# pcb_univ_3-9-0-x-rev3.net
KiCad netlist of a schematic drawn in EAGLE
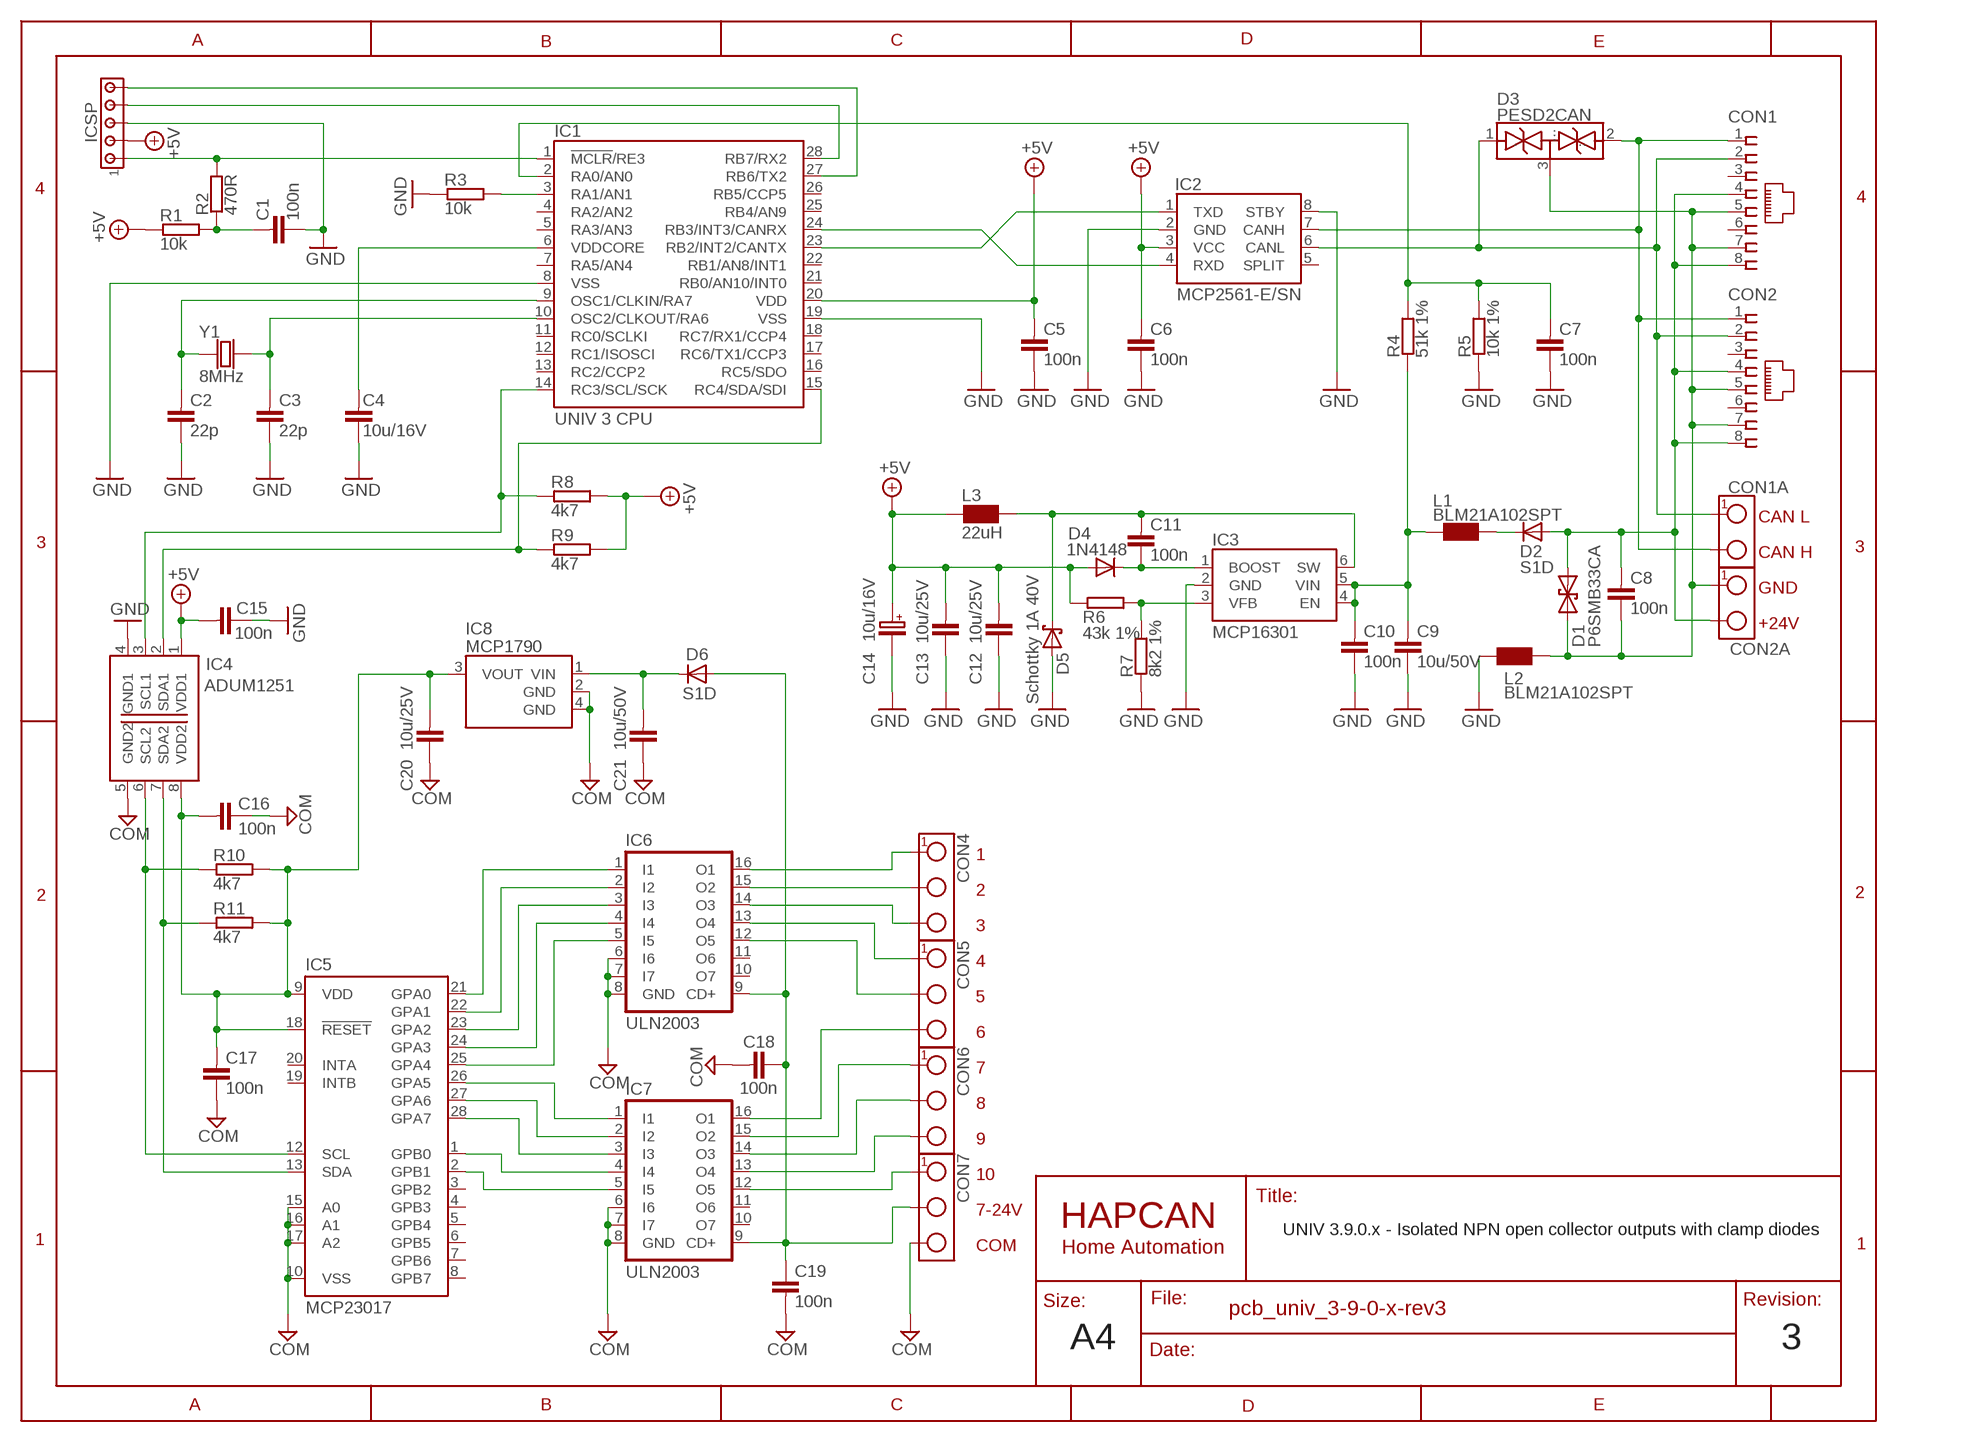
[diagram p0: schematic, sheet 1]

(export (version "E")
  (design (tool "Eeschema 10.0.6"))
  (components
    (comp (ref "C1")
      (value "100n")
      (footprint "eagle-import:0805")
      (libsource (lib "eagle-import") (part "CAPACITOR0805"))
    )
    (comp (ref "C2")
      (value "22p")
      (footprint "eagle-import:0805")
      (libsource (lib "eagle-import") (part "CAPACITOR0805"))
    )
    (comp (ref "C3")
      (value "22p")
      (footprint "eagle-import:0805")
      (libsource (lib "eagle-import") (part "CAPACITOR0805"))
    )
    (comp (ref "C4")
      (value "10u/16V")
      (footprint "eagle-import:0805")
      (libsource (lib "eagle-import") (part "CAPACITOR0805"))
    )
    (comp (ref "C5")
      (value "100n")
      (footprint "eagle-import:0805")
      (libsource (lib "eagle-import") (part "CAPACITOR0805"))
    )
    (comp (ref "C6")
      (value "100n")
      (footprint "eagle-import:0805")
      (libsource (lib "eagle-import") (part "CAPACITOR0805"))
    )
    (comp (ref "C7")
      (value "100n")
      (footprint "eagle-import:0805")
      (libsource (lib "eagle-import") (part "CAPACITOR0805"))
    )
    (comp (ref "C8")
      (value "100n")
      (footprint "eagle-import:0805")
      (libsource (lib "eagle-import") (part "CAPACITOR0805"))
    )
    (comp (ref "C9")
      (value "10u/50V")
      (footprint "eagle-import:1210")
      (libsource (lib "eagle-import") (part "CAPACITOR1210"))
    )
    (comp (ref "C10")
      (value "100n")
      (footprint "eagle-import:0805")
      (libsource (lib "eagle-import") (part "CAPACITOR0805"))
    )
    (comp (ref "C11")
      (value "100n")
      (footprint "eagle-import:0805")
      (libsource (lib "eagle-import") (part "CAPACITOR0805"))
    )
    (comp (ref "C12")
      (value "10u/25V")
      (footprint "eagle-import:1206")
      (libsource (lib "eagle-import") (part "CAPACITOR1206"))
    )
    (comp (ref "C13")
      (value "10u/25V")
      (footprint "eagle-import:1206")
      (libsource (lib "eagle-import") (part "CAPACITOR1206"))
    )
    (comp (ref "C14")
      (value "10u/16V")
      (footprint "eagle-import:SMC_B")
      (libsource (lib "eagle-import") (part "CAPACITOR-POLARIZED-SMC_B"))
    )
    (comp (ref "C15")
      (value "100n")
      (footprint "eagle-import:0805")
      (libsource (lib "eagle-import") (part "CAPACITOR0805"))
    )
    (comp (ref "C16")
      (value "100n")
      (footprint "eagle-import:0805")
      (libsource (lib "eagle-import") (part "CAPACITOR0805"))
    )
    (comp (ref "C17")
      (value "100n")
      (footprint "eagle-import:0805")
      (libsource (lib "eagle-import") (part "CAPACITOR0805"))
    )
    (comp (ref "C18")
      (value "100n")
      (footprint "eagle-import:0805")
      (libsource (lib "eagle-import") (part "CAPACITOR0805"))
    )
    (comp (ref "C19")
      (value "100n")
      (footprint "eagle-import:0805")
      (libsource (lib "eagle-import") (part "CAPACITOR0805"))
    )
    (comp (ref "C20")
      (value "10u/25V")
      (footprint "eagle-import:1206")
      (libsource (lib "eagle-import") (part "CAPACITOR1206"))
    )
    (comp (ref "C21")
      (value "10u/50V")
      (footprint "eagle-import:1210")
      (libsource (lib "eagle-import") (part "CAPACITOR1210"))
    )
    (comp (ref "CON1")
      (value "RJ45-SOCKET")
      (footprint "eagle-import:RJ45-PCB-SOCKET")
      (libsource (lib "eagle-import") (part "RJ45-SOCKET"))
    )
    (comp (ref "CON1A")
      (value "TERMINAL-2")
      (footprint "eagle-import:ARK2-5X10,5MM")
      (libsource (lib "eagle-import") (part "TERMINAL-2-5X10,5MM"))
    )
    (comp (ref "CON2")
      (value "RJ45-SOCKET")
      (footprint "eagle-import:RJ45-PCB-SOCKET")
      (libsource (lib "eagle-import") (part "RJ45-SOCKET"))
    )
    (comp (ref "CON2A")
      (value "TERMINAL-2")
      (footprint "eagle-import:ARK2-5X10,5MM")
      (libsource (lib "eagle-import") (part "TERMINAL-2-5X10,5MM"))
    )
    (comp (ref "CON4")
      (value "TERMINAL-3-3.81X8MM")
      (footprint "eagle-import:ARK3-3.81X8MM")
      (libsource (lib "eagle-import") (part "TERMINAL-3-3.81X8MM"))
    )
    (comp (ref "CON5")
      (value "TERMINAL-3-3.81X8MM")
      (footprint "eagle-import:ARK3-3.81X8MM")
      (libsource (lib "eagle-import") (part "TERMINAL-3-3.81X8MM"))
    )
    (comp (ref "CON6")
      (value "TERMINAL-3-3.81X8MM")
      (footprint "eagle-import:ARK3-3.81X8MM")
      (libsource (lib "eagle-import") (part "TERMINAL-3-3.81X8MM"))
    )
    (comp (ref "CON7")
      (value "TERMINAL-3-3.81X8MM")
      (footprint "eagle-import:ARK3-3.81X8MM")
      (libsource (lib "eagle-import") (part "TERMINAL-3-3.81X8MM"))
    )
    (comp (ref "D1")
      (value "P6SMB33CA")
      (footprint "eagle-import:DO-214_TRANSIL2")
      (libsource (lib "eagle-import") (part "DIODE_TRANSIL2"))
    )
    (comp (ref "D2")
      (value "S1D")
      (footprint "eagle-import:DO-214")
      (libsource (lib "eagle-import") (part "DIODE_DO-214"))
    )
    (comp (ref "D3")
      (value "PESD2CAN")
      (footprint "eagle-import:SOT-23")
      (libsource (lib "eagle-import") (part "PESD2CANSOT-23"))
    )
    (comp (ref "D4")
      (value "1N4148")
      (footprint "eagle-import:0805")
      (libsource (lib "eagle-import") (part "DIODE_0805"))
    )
    (comp (ref "D5")
      (value "Schottky 1A 40V")
      (footprint "eagle-import:DO-214")
      (libsource (lib "eagle-import") (part "DIODE_TRANSIL1_DO214"))
    )
    (comp (ref "D6")
      (value "S1D")
      (footprint "eagle-import:DO-214")
      (libsource (lib "eagle-import") (part "DIODE_DO-214"))
    )
    (comp (ref "IC1")
      (value "UNIV 3 CPU")
      (footprint "eagle-import:UNIV3CPU")
      (libsource (lib "eagle-import") (part "UNIV3CPU-I/SO"))
    )
    (comp (ref "IC2")
      (value "MCP2561-E/SN")
      (footprint "eagle-import:SO-08")
      (libsource (lib "eagle-import") (part "MCP2561-E/SN"))
    )
    (comp (ref "IC3")
      (value "MCP16301")
      (footprint "eagle-import:SOT-23-6")
      (libsource (lib "eagle-import") (part "MCP16301SOT23-6"))
    )
    (comp (ref "IC4")
      (value "ADUM1251")
      (footprint "eagle-import:SO-08")
      (libsource (lib "eagle-import") (part "ADUM1251"))
    )
    (comp (ref "IC5")
      (value "MCP23017")
      (footprint "eagle-import:SO-28W")
      (libsource (lib "eagle-import") (part "MCP23017-SO"))
    )
    (comp (ref "IC6")
      (value "ULN2003")
      (footprint "eagle-import:SO-16")
      (libsource (lib "eagle-import") (part "ULN2003"))
    )
    (comp (ref "IC7")
      (value "ULN2003")
      (footprint "eagle-import:SO-16")
      (libsource (lib "eagle-import") (part "ULN2003"))
    )
    (comp (ref "IC8")
      (value "MCP1790")
      (footprint "eagle-import:SOT-223")
      (libsource (lib "eagle-import") (part "MCP1790"))
    )
    (comp (ref "ICSP")
      (value "HEADER5")
      (footprint "eagle-import:SIP-5")
      (libsource (lib "eagle-import") (part "HEADER5"))
    )
    (comp (ref "L1")
      (value "BLM21A102SPT")
      (footprint "eagle-import:0805")
      (libsource (lib "eagle-import") (part "CHOKE0805"))
    )
    (comp (ref "L2")
      (value "BLM21A102SPT")
      (footprint "eagle-import:0805")
      (libsource (lib "eagle-import") (part "CHOKE0805"))
    )
    (comp (ref "L3")
      (value "22uH")
      (footprint "eagle-import:CHOKE-DER0705")
      (libsource (lib "eagle-import") (part "CHOKEDER0705"))
    )
    (comp (ref "R1")
      (value "10k")
      (footprint "eagle-import:0805")
      (libsource (lib "eagle-import") (part "RESISTOR0805"))
    )
    (comp (ref "R2")
      (value "470R")
      (footprint "eagle-import:0805")
      (libsource (lib "eagle-import") (part "RESISTOR0805"))
    )
    (comp (ref "R3")
      (value "10k")
      (footprint "eagle-import:0805")
      (libsource (lib "eagle-import") (part "RESISTOR0805"))
    )
    (comp (ref "R4")
      (value "51k 1%")
      (footprint "eagle-import:0805")
      (libsource (lib "eagle-import") (part "RESISTOR0805"))
    )
    (comp (ref "R5")
      (value "10k 1%")
      (footprint "eagle-import:0805")
      (libsource (lib "eagle-import") (part "RESISTOR0805"))
    )
    (comp (ref "R6")
      (value "43k 1%")
      (footprint "eagle-import:0805")
      (libsource (lib "eagle-import") (part "RESISTOR0805"))
    )
    (comp (ref "R7")
      (value "8k2 1%")
      (footprint "eagle-import:0805")
      (libsource (lib "eagle-import") (part "RESISTOR0805"))
    )
    (comp (ref "R8")
      (value "4k7")
      (footprint "eagle-import:0805")
      (libsource (lib "eagle-import") (part "RESISTOR0805"))
    )
    (comp (ref "R9")
      (value "4k7")
      (footprint "eagle-import:0805")
      (libsource (lib "eagle-import") (part "RESISTOR0805"))
    )
    (comp (ref "R10")
      (value "4k7")
      (footprint "eagle-import:0805")
      (libsource (lib "eagle-import") (part "RESISTOR0805"))
    )
    (comp (ref "R11")
      (value "4k7")
      (footprint "eagle-import:0805")
      (libsource (lib "eagle-import") (part "RESISTOR0805"))
    )
    (comp (ref "Y1")
      (value "8MHz")
      (footprint "eagle-import:CRYSTAL-HC49V")
      (libsource (lib "eagle-import") (part "CRYSTAL-HC49V"))
    )
  )
  (nets
    (net (code "1") (name "+5V") (class "Default")
      (node (ref "C12") (pin "1") (pinfunction "1_1") (pintype "passive"))
      (node (ref "C13") (pin "1") (pinfunction "1_1") (pintype "passive"))
      (node (ref "C14") (pin "+") (pinfunction "1_+") (pintype "passive"))
      (node (ref "C15") (pin "1") (pinfunction "1_1") (pintype "passive"))
      (node (ref "C5") (pin "1") (pinfunction "1_1") (pintype "passive"))
      (node (ref "C6") (pin "1") (pinfunction "1_1") (pintype "passive"))
      (node (ref "D4") (pin "2") (pinfunction "A_2") (pintype "passive"))
      (node (ref "IC1") (pin "20") (pinfunction "VDD_20") (pintype "bidirectional"))
      (node (ref "IC2") (pin "3") (pinfunction "VCC_3") (pintype "bidirectional"))
      (node (ref "IC4") (pin "1") (pinfunction "VDD1_1") (pintype "bidirectional"))
      (node (ref "ICSP") (pin "2") (pinfunction "2_2") (pintype "passive"))
      (node (ref "L3") (pin "1") (pinfunction "1_1") (pintype "passive"))
      (node (ref "R1") (pin "1") (pinfunction "1_1") (pintype "passive"))
      (node (ref "R6") (pin "1") (pinfunction "1_1") (pintype "passive"))
      (node (ref "R8") (pin "2") (pinfunction "2_2") (pintype "passive"))
      (node (ref "R9") (pin "2") (pinfunction "2_2") (pintype "passive"))
    )
    (net (code "2") (name "COM") (class "Default")
      (node (ref "C16") (pin "2") (pinfunction "2_2") (pintype "passive"))
      (node (ref "C17") (pin "2") (pinfunction "2_2") (pintype "passive"))
      (node (ref "C18") (pin "1") (pinfunction "1_1") (pintype "passive"))
      (node (ref "C19") (pin "1") (pinfunction "1_1") (pintype "passive"))
      (node (ref "C20") (pin "2") (pinfunction "2_2") (pintype "passive"))
      (node (ref "C21") (pin "2") (pinfunction "2_2") (pintype "passive"))
      (node (ref "CON7") (pin "3") (pinfunction "3_3") (pintype "passive"))
      (node (ref "IC4") (pin "5") (pinfunction "GND2_5") (pintype "bidirectional"))
      (node (ref "IC5") (pin "10") (pinfunction "VSS_10") (pintype "bidirectional"))
      (node (ref "IC5") (pin "15") (pinfunction "A0_15") (pintype "input"))
      (node (ref "IC5") (pin "16") (pinfunction "A1_16") (pintype "input"))
      (node (ref "IC5") (pin "17") (pinfunction "A2_17") (pintype "input"))
      (node (ref "IC6") (pin "6") (pinfunction "I6_6") (pintype "input"))
      (node (ref "IC6") (pin "7") (pinfunction "I7_7") (pintype "input"))
      (node (ref "IC6") (pin "8") (pinfunction "GND_8") (pintype "power_in"))
      (node (ref "IC7") (pin "6") (pinfunction "I6_6") (pintype "input"))
      (node (ref "IC7") (pin "7") (pinfunction "I7_7") (pintype "input"))
      (node (ref "IC7") (pin "8") (pinfunction "GND_8") (pintype "power_in"))
      (node (ref "IC8") (pin "2") (pinfunction "GND_2") (pintype "bidirectional"))
      (node (ref "IC8") (pin "4") (pinfunction "GND_4") (pintype "bidirectional"))
    )
    (net (code "3") (name "GND") (class "Default")
      (node (ref "C1") (pin "2") (pinfunction "2_2") (pintype "passive"))
      (node (ref "C10") (pin "2") (pinfunction "2_2") (pintype "passive"))
      (node (ref "C12") (pin "2") (pinfunction "2_2") (pintype "passive"))
      (node (ref "C13") (pin "2") (pinfunction "2_2") (pintype "passive"))
      (node (ref "C14") (pin "-") (pinfunction "2_-") (pintype "passive"))
      (node (ref "C15") (pin "2") (pinfunction "2_2") (pintype "passive"))
      (node (ref "C2") (pin "2") (pinfunction "2_2") (pintype "passive"))
      (node (ref "C3") (pin "2") (pinfunction "2_2") (pintype "passive"))
      (node (ref "C4") (pin "2") (pinfunction "2_2") (pintype "passive"))
      (node (ref "C5") (pin "2") (pinfunction "2_2") (pintype "passive"))
      (node (ref "C6") (pin "2") (pinfunction "2_2") (pintype "passive"))
      (node (ref "C7") (pin "2") (pinfunction "2_2") (pintype "passive"))
      (node (ref "C9") (pin "2") (pinfunction "2_2") (pintype "passive"))
      (node (ref "D5") (pin "A") (pinfunction "A_A") (pintype "passive"))
      (node (ref "IC1") (pin "19") (pinfunction "VSS_19") (pintype "bidirectional"))
      (node (ref "IC1") (pin "8") (pinfunction "VSS_8") (pintype "bidirectional"))
      (node (ref "IC2") (pin "2") (pinfunction "GND_2") (pintype "bidirectional"))
      (node (ref "IC2") (pin "8") (pinfunction "STBY_8") (pintype "bidirectional"))
      (node (ref "IC3") (pin "2") (pinfunction "GND_2") (pintype "bidirectional"))
      (node (ref "IC4") (pin "4") (pinfunction "GND1_4") (pintype "bidirectional"))
      (node (ref "ICSP") (pin "3") (pinfunction "3_3") (pintype "passive"))
      (node (ref "L2") (pin "1") (pinfunction "1_1") (pintype "passive"))
      (node (ref "R3") (pin "1") (pinfunction "1_1") (pintype "passive"))
      (node (ref "R5") (pin "1") (pinfunction "1_1") (pintype "passive"))
      (node (ref "R7") (pin "1") (pinfunction "1_1") (pintype "passive"))
    )
    (net (code "4") (name "Net-(C1-Pad1)") (class "Default")
      (node (ref "C1") (pin "1") (pinfunction "1_1") (pintype "passive"))
      (node (ref "R1") (pin "2") (pinfunction "2_2") (pintype "passive"))
      (node (ref "R2") (pin "1") (pinfunction "1_1") (pintype "passive"))
    )
    (net (code "5") (name "Net-(D1-1)") (class "Default")
      (node (ref "C8") (pin "2") (pinfunction "2_2") (pintype "passive"))
      (node (ref "CON1") (pin "5") (pinfunction "5_5") (pintype "passive"))
      (node (ref "CON1") (pin "7") (pinfunction "7_7") (pintype "passive"))
      (node (ref "CON2") (pin "5") (pinfunction "5_5") (pintype "passive"))
      (node (ref "CON2") (pin "7") (pinfunction "7_7") (pintype "passive"))
      (node (ref "CON2A") (pin "1") (pinfunction "1_1") (pintype "passive"))
      (node (ref "D1") (pin "A") (pinfunction "1_A") (pintype "passive"))
      (node (ref "D3") (pin "3") (pinfunction "..._3") (pintype "bidirectional"))
      (node (ref "L2") (pin "2") (pinfunction "2_2") (pintype "passive"))
    )
    (net (code "6") (name "Net-(D1-2)") (class "Default")
      (node (ref "C8") (pin "1") (pinfunction "1_1") (pintype "passive"))
      (node (ref "CON1") (pin "4") (pinfunction "4_4") (pintype "passive"))
      (node (ref "CON1") (pin "8") (pinfunction "8_8") (pintype "passive"))
      (node (ref "CON2") (pin "4") (pinfunction "4_4") (pintype "passive"))
      (node (ref "CON2") (pin "8") (pinfunction "8_8") (pintype "passive"))
      (node (ref "CON2A") (pin "2") (pinfunction "2_2") (pintype "passive"))
      (node (ref "D1") (pin "C") (pinfunction "2_C") (pintype "passive"))
      (node (ref "D2") (pin "A") (pinfunction "A_A") (pintype "passive"))
    )
    (net (code "7") (name "Net-(D2-PadC)") (class "Default")
      (node (ref "D2") (pin "C") (pinfunction "C_C") (pintype "passive"))
      (node (ref "L1") (pin "2") (pinfunction "2_2") (pintype "passive"))
    )
    (net (code "8") (name "Net-(D3-.)") (class "Default")
      (node (ref "CON1") (pin "2") (pinfunction "2_2") (pintype "passive"))
      (node (ref "CON1A") (pin "1") (pinfunction "1_1") (pintype "passive"))
      (node (ref "CON2") (pin "2") (pinfunction "2_2") (pintype "passive"))
      (node (ref "D3") (pin "1") (pinfunction "._1") (pintype "bidirectional"))
      (node (ref "IC2") (pin "6") (pinfunction "CANL_6") (pintype "bidirectional"))
    )
    (net (code "9") (name "Net-(D3-..)") (class "Default")
      (node (ref "CON1") (pin "1") (pinfunction "1_1") (pintype "passive"))
      (node (ref "CON1A") (pin "2") (pinfunction "2_2") (pintype "passive"))
      (node (ref "CON2") (pin "1") (pinfunction "1_1") (pintype "passive"))
      (node (ref "D3") (pin "2") (pinfunction ".._2") (pintype "bidirectional"))
      (node (ref "IC2") (pin "7") (pinfunction "CANH_7") (pintype "bidirectional"))
    )
    (net (code "10") (name "Net-(D4-C)") (class "Default")
      (node (ref "C11") (pin "2") (pinfunction "2_2") (pintype "passive"))
      (node (ref "D4") (pin "1") (pinfunction "C_1") (pintype "passive"))
      (node (ref "IC3") (pin "1") (pinfunction "BOOST_1") (pintype "bidirectional"))
    )
    (net (code "11") (name "Net-(IC1-OSC1{slash}CLKIN{slash}RA7)") (class "Default")
      (node (ref "C2") (pin "1") (pinfunction "1_1") (pintype "passive"))
      (node (ref "IC1") (pin "9") (pinfunction "OSC1/CLKIN/RA7_9") (pintype "bidirectional"))
      (node (ref "Y1") (pin "1") (pinfunction "1_1") (pintype "passive"))
    )
    (net (code "12") (name "Net-(IC1-OSC2{slash}CLKOUT{slash}RA6)") (class "Default")
      (node (ref "C3") (pin "1") (pinfunction "1_1") (pintype "passive"))
      (node (ref "IC1") (pin "10") (pinfunction "OSC2/CLKOUT/RA6_10") (pintype "bidirectional"))
      (node (ref "Y1") (pin "2") (pinfunction "2_2") (pintype "passive"))
    )
    (net (code "13") (name "Net-(IC1-RA0{slash}AN0)") (class "Default")
      (node (ref "C7") (pin "1") (pinfunction "1_1") (pintype "passive"))
      (node (ref "IC1") (pin "2") (pinfunction "RA0/AN0_2") (pintype "bidirectional"))
      (node (ref "R4") (pin "2") (pinfunction "2_2") (pintype "passive"))
      (node (ref "R5") (pin "2") (pinfunction "2_2") (pintype "passive"))
    )
    (net (code "14") (name "Net-(IC1-RA1{slash}AN1)") (class "Default")
      (node (ref "IC1") (pin "3") (pinfunction "RA1/AN1_3") (pintype "bidirectional"))
      (node (ref "R3") (pin "2") (pinfunction "2_2") (pintype "passive"))
    )
    (net (code "15") (name "Net-(IC1-RB2{slash}INT2{slash}CANTX)") (class "Default")
      (node (ref "IC1") (pin "23") (pinfunction "RB2/INT2/CANTX_23") (pintype "bidirectional"))
      (node (ref "IC2") (pin "1") (pinfunction "TXD_1") (pintype "bidirectional"))
    )
    (net (code "16") (name "Net-(IC1-RB3{slash}INT3{slash}CANRX)") (class "Default")
      (node (ref "IC1") (pin "24") (pinfunction "RB3/INT3/CANRX_24") (pintype "bidirectional"))
      (node (ref "IC2") (pin "4") (pinfunction "RXD_4") (pintype "bidirectional"))
    )
    (net (code "17") (name "Net-(IC1-RB6{slash}TX2)") (class "Default")
      (node (ref "IC1") (pin "27") (pinfunction "RB6/TX2_27") (pintype "bidirectional"))
      (node (ref "ICSP") (pin "5") (pinfunction "5_5") (pintype "passive"))
    )
    (net (code "18") (name "Net-(IC1-RB7{slash}RX2)") (class "Default")
      (node (ref "IC1") (pin "28") (pinfunction "RB7/RX2_28") (pintype "bidirectional"))
      (node (ref "ICSP") (pin "4") (pinfunction "4_4") (pintype "passive"))
    )
    (net (code "19") (name "Net-(IC1-RC3{slash}SCL{slash}SCK)") (class "Default")
      (node (ref "IC1") (pin "14") (pinfunction "RC3/SCL/SCK_14") (pintype "bidirectional"))
      (node (ref "IC4") (pin "3") (pinfunction "SCL1_3") (pintype "input"))
      (node (ref "R8") (pin "1") (pinfunction "1_1") (pintype "passive"))
    )
    (net (code "20") (name "Net-(IC1-RC4{slash}SDA{slash}SDI)") (class "Default")
      (node (ref "IC1") (pin "15") (pinfunction "RC4/SDA/SDI_15") (pintype "bidirectional"))
      (node (ref "IC4") (pin "2") (pinfunction "SDA1_2") (pintype "bidirectional"))
      (node (ref "R9") (pin "1") (pinfunction "1_1") (pintype "passive"))
    )
    (net (code "21") (name "Net-(IC1-VDDCORE)") (class "Default")
      (node (ref "C4") (pin "1") (pinfunction "1_1") (pintype "passive"))
      (node (ref "IC1") (pin "6") (pinfunction "VDDCORE_6") (pintype "bidirectional"))
    )
    (net (code "22") (name "Net-(IC1-~{MCLR}{slash}RE3)") (class "Default")
      (node (ref "IC1") (pin "1") (pinfunction "~{MCLR}/RE3_1") (pintype "bidirectional"))
      (node (ref "ICSP") (pin "1") (pinfunction "1_1") (pintype "passive"))
      (node (ref "R2") (pin "2") (pinfunction "2_2") (pintype "passive"))
    )
    (net (code "23") (name "Net-(IC3-EN)") (class "Default")
      (node (ref "C10") (pin "1") (pinfunction "1_1") (pintype "passive"))
      (node (ref "C9") (pin "1") (pinfunction "1_1") (pintype "passive"))
      (node (ref "IC3") (pin "4") (pinfunction "EN_4") (pintype "bidirectional"))
      (node (ref "IC3") (pin "5") (pinfunction "VIN_5") (pintype "bidirectional"))
      (node (ref "L1") (pin "1") (pinfunction "1_1") (pintype "passive"))
      (node (ref "R4") (pin "1") (pinfunction "1_1") (pintype "passive"))
    )
    (net (code "24") (name "Net-(IC3-SW)") (class "Default")
      (node (ref "C11") (pin "1") (pinfunction "1_1") (pintype "passive"))
      (node (ref "D5") (pin "C") (pinfunction "C_C") (pintype "passive"))
      (node (ref "IC3") (pin "6") (pinfunction "SW_6") (pintype "bidirectional"))
      (node (ref "L3") (pin "2") (pinfunction "2_2") (pintype "passive"))
    )
    (net (code "25") (name "Net-(IC3-VFB)") (class "Default")
      (node (ref "IC3") (pin "3") (pinfunction "VFB_3") (pintype "bidirectional"))
      (node (ref "R6") (pin "2") (pinfunction "2_2") (pintype "passive"))
      (node (ref "R7") (pin "2") (pinfunction "2_2") (pintype "passive"))
    )
    (net (code "26") (name "Net-(IC4-SCL2)") (class "Default")
      (node (ref "IC4") (pin "6") (pinfunction "SCL2_6") (pintype "output"))
      (node (ref "IC5") (pin "12") (pinfunction "SCL_12") (pintype "input"))
      (node (ref "R10") (pin "1") (pinfunction "1_1") (pintype "passive"))
    )
    (net (code "27") (name "Net-(IC4-SDA2)") (class "Default")
      (node (ref "IC4") (pin "7") (pinfunction "SDA2_7") (pintype "bidirectional"))
      (node (ref "IC5") (pin "13") (pinfunction "SDA_13") (pintype "bidirectional"))
      (node (ref "R11") (pin "1") (pinfunction "1_1") (pintype "passive"))
    )
    (net (code "28") (name "Net-(IC4-VDD2)") (class "Default")
      (node (ref "C16") (pin "1") (pinfunction "1_1") (pintype "passive"))
      (node (ref "C17") (pin "1") (pinfunction "1_1") (pintype "passive"))
      (node (ref "C20") (pin "1") (pinfunction "1_1") (pintype "passive"))
      (node (ref "IC4") (pin "8") (pinfunction "VDD2_8") (pintype "bidirectional"))
      (node (ref "IC5") (pin "18") (pinfunction "~{RESET}_18") (pintype "input"))
      (node (ref "IC5") (pin "9") (pinfunction "VDD_9") (pintype "bidirectional"))
      (node (ref "IC8") (pin "3") (pinfunction "VOUT_3") (pintype "bidirectional"))
      (node (ref "R10") (pin "2") (pinfunction "2_2") (pintype "passive"))
      (node (ref "R11") (pin "2") (pinfunction "2_2") (pintype "passive"))
    )
    (net (code "29") (name "Net-(IC5-GPA0)") (class "Default")
      (node (ref "IC5") (pin "21") (pinfunction "GPA0_21") (pintype "bidirectional"))
      (node (ref "IC6") (pin "1") (pinfunction "I1_1") (pintype "input"))
    )
    (net (code "30") (name "Net-(IC5-GPA1)") (class "Default")
      (node (ref "IC5") (pin "22") (pinfunction "GPA1_22") (pintype "bidirectional"))
      (node (ref "IC6") (pin "2") (pinfunction "I2_2") (pintype "input"))
    )
    (net (code "31") (name "Net-(IC5-GPA2)") (class "Default")
      (node (ref "IC5") (pin "23") (pinfunction "GPA2_23") (pintype "bidirectional"))
      (node (ref "IC6") (pin "3") (pinfunction "I3_3") (pintype "input"))
    )
    (net (code "32") (name "Net-(IC5-GPA3)") (class "Default")
      (node (ref "IC5") (pin "24") (pinfunction "GPA3_24") (pintype "bidirectional"))
      (node (ref "IC6") (pin "4") (pinfunction "I4_4") (pintype "input"))
    )
    (net (code "33") (name "Net-(IC5-GPA4)") (class "Default")
      (node (ref "IC5") (pin "25") (pinfunction "GPA4_25") (pintype "bidirectional"))
      (node (ref "IC6") (pin "5") (pinfunction "I5_5") (pintype "input"))
    )
    (net (code "34") (name "Net-(IC5-GPA5)") (class "Default")
      (node (ref "IC5") (pin "26") (pinfunction "GPA5_26") (pintype "bidirectional"))
      (node (ref "IC7") (pin "1") (pinfunction "I1_1") (pintype "input"))
    )
    (net (code "35") (name "Net-(IC5-GPA6)") (class "Default")
      (node (ref "IC5") (pin "27") (pinfunction "GPA6_27") (pintype "bidirectional"))
      (node (ref "IC7") (pin "2") (pinfunction "I2_2") (pintype "input"))
    )
    (net (code "36") (name "Net-(IC5-GPA7)") (class "Default")
      (node (ref "IC5") (pin "28") (pinfunction "GPA7_28") (pintype "bidirectional"))
      (node (ref "IC7") (pin "3") (pinfunction "I3_3") (pintype "input"))
    )
    (net (code "37") (name "Net-(IC5-GPB0)") (class "Default")
      (node (ref "IC5") (pin "1") (pinfunction "GPB0_1") (pintype "bidirectional"))
      (node (ref "IC7") (pin "4") (pinfunction "I4_4") (pintype "input"))
    )
    (net (code "38") (name "Net-(IC5-GPB1)") (class "Default")
      (node (ref "IC5") (pin "2") (pinfunction "GPB1_2") (pintype "bidirectional"))
      (node (ref "IC7") (pin "5") (pinfunction "I5_5") (pintype "input"))
    )
    (net (code "39") (name "Net-(IC6-CD+)") (class "Default")
      (node (ref "C18") (pin "2") (pinfunction "2_2") (pintype "passive"))
      (node (ref "C19") (pin "2") (pinfunction "2_2") (pintype "passive"))
      (node (ref "CON7") (pin "2") (pinfunction "2_2") (pintype "passive"))
      (node (ref "D6") (pin "A") (pinfunction "A_A") (pintype "passive"))
      (node (ref "IC6") (pin "9") (pinfunction "CD+_9") (pintype "passive"))
      (node (ref "IC7") (pin "9") (pinfunction "CD+_9") (pintype "passive"))
    )
    (net (code "40") (name "Net-(IC6-O1)") (class "Default")
      (node (ref "CON4") (pin "1") (pinfunction "1_1") (pintype "passive"))
      (node (ref "IC6") (pin "16") (pinfunction "O1_16") (pintype "open_collector"))
    )
    (net (code "41") (name "Net-(IC6-O2)") (class "Default")
      (node (ref "CON4") (pin "2") (pinfunction "2_2") (pintype "passive"))
      (node (ref "IC6") (pin "15") (pinfunction "O2_15") (pintype "open_collector"))
    )
    (net (code "42") (name "Net-(IC6-O3)") (class "Default")
      (node (ref "CON4") (pin "3") (pinfunction "3_3") (pintype "passive"))
      (node (ref "IC6") (pin "14") (pinfunction "O3_14") (pintype "open_collector"))
    )
    (net (code "43") (name "Net-(IC6-O4)") (class "Default")
      (node (ref "CON5") (pin "1") (pinfunction "1_1") (pintype "passive"))
      (node (ref "IC6") (pin "13") (pinfunction "O4_13") (pintype "open_collector"))
    )
    (net (code "44") (name "Net-(IC6-O5)") (class "Default")
      (node (ref "CON5") (pin "2") (pinfunction "2_2") (pintype "passive"))
      (node (ref "IC6") (pin "12") (pinfunction "O5_12") (pintype "open_collector"))
    )
    (net (code "45") (name "Net-(IC7-O1)") (class "Default")
      (node (ref "CON5") (pin "3") (pinfunction "3_3") (pintype "passive"))
      (node (ref "IC7") (pin "16") (pinfunction "O1_16") (pintype "open_collector"))
    )
    (net (code "46") (name "Net-(IC7-O2)") (class "Default")
      (node (ref "CON6") (pin "1") (pinfunction "1_1") (pintype "passive"))
      (node (ref "IC7") (pin "15") (pinfunction "O2_15") (pintype "open_collector"))
    )
    (net (code "47") (name "Net-(IC7-O3)") (class "Default")
      (node (ref "CON6") (pin "2") (pinfunction "2_2") (pintype "passive"))
      (node (ref "IC7") (pin "14") (pinfunction "O3_14") (pintype "open_collector"))
    )
    (net (code "48") (name "Net-(IC7-O4)") (class "Default")
      (node (ref "CON6") (pin "3") (pinfunction "3_3") (pintype "passive"))
      (node (ref "IC7") (pin "13") (pinfunction "O4_13") (pintype "open_collector"))
    )
    (net (code "49") (name "Net-(IC7-O5)") (class "Default")
      (node (ref "CON7") (pin "1") (pinfunction "1_1") (pintype "passive"))
      (node (ref "IC7") (pin "12") (pinfunction "O5_12") (pintype "open_collector"))
    )
    (net (code "50") (name "Net-(IC8-VIN)") (class "Default")
      (node (ref "C21") (pin "1") (pinfunction "1_1") (pintype "passive"))
      (node (ref "D6") (pin "C") (pinfunction "C_C") (pintype "passive"))
      (node (ref "IC8") (pin "1") (pinfunction "VIN_1") (pintype "bidirectional"))
    )
    (net (code "51") (name "unconnected-(CON1-Pad3)") (class "Default")
      (node (ref "CON1") (pin "3") (pinfunction "3_3") (pintype "passive"))
    )
    (net (code "52") (name "unconnected-(CON1-Pad6)") (class "Default")
      (node (ref "CON1") (pin "6") (pinfunction "6_6") (pintype "passive"))
    )
    (net (code "53") (name "unconnected-(CON2-Pad3)") (class "Default")
      (node (ref "CON2") (pin "3") (pinfunction "3_3") (pintype "passive"))
    )
    (net (code "54") (name "unconnected-(CON2-Pad6)") (class "Default")
      (node (ref "CON2") (pin "6") (pinfunction "6_6") (pintype "passive"))
    )
    (net (code "55") (name "unconnected-(IC1-RA2{slash}AN2-Pad4)") (class "Default")
      (node (ref "IC1") (pin "4") (pinfunction "RA2/AN2_4") (pintype "bidirectional"))
    )
    (net (code "56") (name "unconnected-(IC1-RA3{slash}AN3-Pad5)") (class "Default")
      (node (ref "IC1") (pin "5") (pinfunction "RA3/AN3_5") (pintype "bidirectional"))
    )
    (net (code "57") (name "unconnected-(IC1-RA5{slash}AN4-Pad7)") (class "Default")
      (node (ref "IC1") (pin "7") (pinfunction "RA5/AN4_7") (pintype "bidirectional"))
    )
    (net (code "58") (name "unconnected-(IC1-RB0{slash}AN10{slash}INT0-Pad21)") (class "Default")
      (node (ref "IC1") (pin "21") (pinfunction "RB0/AN10/INT0_21") (pintype "bidirectional"))
    )
    (net (code "59") (name "unconnected-(IC1-RB1{slash}AN8{slash}INT1-Pad22)") (class "Default")
      (node (ref "IC1") (pin "22") (pinfunction "RB1/AN8/INT1_22") (pintype "bidirectional"))
    )
    (net (code "60") (name "unconnected-(IC1-RB4{slash}AN9-Pad25)") (class "Default")
      (node (ref "IC1") (pin "25") (pinfunction "RB4/AN9_25") (pintype "bidirectional"))
    )
    (net (code "61") (name "unconnected-(IC1-RB5{slash}CCP5-Pad26)") (class "Default")
      (node (ref "IC1") (pin "26") (pinfunction "RB5/CCP5_26") (pintype "bidirectional"))
    )
    (net (code "62") (name "unconnected-(IC1-RC0{slash}SCLKI-Pad11)") (class "Default")
      (node (ref "IC1") (pin "11") (pinfunction "RC0/SCLKI_11") (pintype "bidirectional"))
    )
    (net (code "63") (name "unconnected-(IC1-RC1{slash}ISOSCI-Pad12)") (class "Default")
      (node (ref "IC1") (pin "12") (pinfunction "RC1/ISOSCI_12") (pintype "bidirectional"))
    )
    (net (code "64") (name "unconnected-(IC1-RC2{slash}CCP2-Pad13)") (class "Default")
      (node (ref "IC1") (pin "13") (pinfunction "RC2/CCP2_13") (pintype "bidirectional"))
    )
    (net (code "65") (name "unconnected-(IC1-RC5{slash}SDO-Pad16)") (class "Default")
      (node (ref "IC1") (pin "16") (pinfunction "RC5/SDO_16") (pintype "bidirectional"))
    )
    (net (code "66") (name "unconnected-(IC1-RC6{slash}TX1{slash}CCP3-Pad17)") (class "Default")
      (node (ref "IC1") (pin "17") (pinfunction "RC6/TX1/CCP3_17") (pintype "bidirectional"))
    )
    (net (code "67") (name "unconnected-(IC1-RC7{slash}RX1{slash}CCP4-Pad18)") (class "Default")
      (node (ref "IC1") (pin "18") (pinfunction "RC7/RX1/CCP4_18") (pintype "bidirectional"))
    )
    (net (code "68") (name "unconnected-(IC2-SPLIT-Pad5)") (class "Default")
      (node (ref "IC2") (pin "5") (pinfunction "SPLIT_5") (pintype "bidirectional"))
    )
    (net (code "69") (name "unconnected-(IC5-GPB2-Pad3)") (class "Default")
      (node (ref "IC5") (pin "3") (pinfunction "GPB2_3") (pintype "bidirectional"))
    )
    (net (code "70") (name "unconnected-(IC5-GPB3-Pad4)") (class "Default")
      (node (ref "IC5") (pin "4") (pinfunction "GPB3_4") (pintype "bidirectional"))
    )
    (net (code "71") (name "unconnected-(IC5-GPB4-Pad5)") (class "Default")
      (node (ref "IC5") (pin "5") (pinfunction "GPB4_5") (pintype "bidirectional"))
    )
    (net (code "72") (name "unconnected-(IC5-GPB5-Pad6)") (class "Default")
      (node (ref "IC5") (pin "6") (pinfunction "GPB5_6") (pintype "bidirectional"))
    )
    (net (code "73") (name "unconnected-(IC5-GPB6-Pad7)") (class "Default")
      (node (ref "IC5") (pin "7") (pinfunction "GPB6_7") (pintype "bidirectional"))
    )
    (net (code "74") (name "unconnected-(IC5-GPB7-Pad8)") (class "Default")
      (node (ref "IC5") (pin "8") (pinfunction "GPB7_8") (pintype "bidirectional"))
    )
    (net (code "75") (name "unconnected-(IC5-INTA-Pad20)") (class "Default")
      (node (ref "IC5") (pin "20") (pinfunction "INTA_20") (pintype "output"))
    )
    (net (code "76") (name "unconnected-(IC5-INTB-Pad19)") (class "Default")
      (node (ref "IC5") (pin "19") (pinfunction "INTB_19") (pintype "output"))
    )
    (net (code "77") (name "unconnected-(IC6-O6-Pad11)") (class "Default")
      (node (ref "IC6") (pin "11") (pinfunction "O6_11") (pintype "open_collector"))
    )
    (net (code "78") (name "unconnected-(IC6-O7-Pad10)") (class "Default")
      (node (ref "IC6") (pin "10") (pinfunction "O7_10") (pintype "open_collector"))
    )
    (net (code "79") (name "unconnected-(IC7-O6-Pad11)") (class "Default")
      (node (ref "IC7") (pin "11") (pinfunction "O6_11") (pintype "open_collector"))
    )
    (net (code "80") (name "unconnected-(IC7-O7-Pad10)") (class "Default")
      (node (ref "IC7") (pin "10") (pinfunction "O7_10") (pintype "open_collector"))
    )
  )
)
